# GyroscopeBreakout.net
KiCad netlist of a schematic drawn in Altium Designer
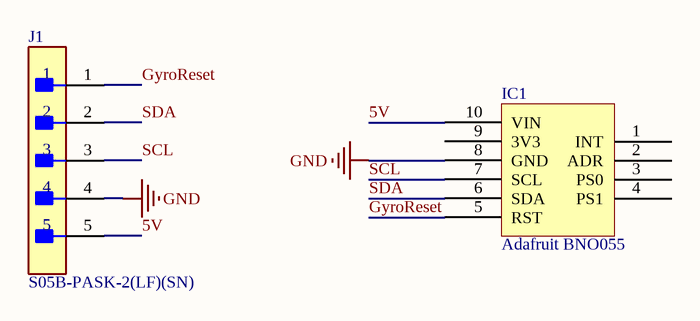
[diagram p0: GyroscopeBreakout.SchDoc]

(export (version "E")
  (design (tool "Eeschema 10.0.6"))
  (components
    (comp (ref "IC1")
      (value "Adafruit BNO055")
      (footprint "Adafruit BNO055-Footprint-1")
      (libsource (lib "Jouveer") (part "Adafruit BNO055-Symbol-1"))
    )
    (comp (ref "J1")
      (value "S05B-PASK-2(LF)(SN)")
      (footprint "FP-S05B-PASK-2_LF_SN-MFG")
      (description "CONN HEADER R/A 5POS 2MM")
      (libsource (lib "Altium Content Vault") (part "bf93c07fd2649a848d0ec8585582aab"))
    )
  )
  (nets
    (net (code "1") (name "/5V") (class "Default")
      (node (ref "IC1") (pin "10") (pinfunction "VIN_10") (pintype "passive"))
      (node (ref "J1") (pin "5") (pinfunction "5_5") (pintype "passive"))
    )
    (net (code "2") (name "/GyroReset") (class "Default")
      (node (ref "IC1") (pin "5") (pinfunction "RST_5") (pintype "passive"))
      (node (ref "J1") (pin "1") (pinfunction "1_1") (pintype "passive"))
    )
    (net (code "3") (name "/SCL") (class "Default")
      (node (ref "IC1") (pin "7") (pinfunction "SCL_7") (pintype "passive"))
      (node (ref "J1") (pin "3") (pinfunction "3_3") (pintype "passive"))
    )
    (net (code "4") (name "/SDA") (class "Default")
      (node (ref "IC1") (pin "6") (pinfunction "SDA_6") (pintype "passive"))
      (node (ref "J1") (pin "2") (pinfunction "2_2") (pintype "passive"))
    )
    (net (code "5") (name "GND") (class "Default")
      (node (ref "IC1") (pin "8") (pinfunction "GND_8") (pintype "passive"))
      (node (ref "J1") (pin "4") (pinfunction "4_4") (pintype "passive"))
    )
    (net (code "6") (name "unconnected-(IC1-3V3-Pad9)") (class "Default")
      (node (ref "IC1") (pin "9") (pinfunction "3V3_9") (pintype "passive"))
    )
    (net (code "7") (name "unconnected-(IC1-ADR-Pad2)") (class "Default")
      (node (ref "IC1") (pin "2") (pinfunction "ADR_2") (pintype "passive"))
    )
    (net (code "8") (name "unconnected-(IC1-INT-Pad1)") (class "Default")
      (node (ref "IC1") (pin "1") (pinfunction "INT_1") (pintype "passive"))
    )
    (net (code "9") (name "unconnected-(IC1-PS0-Pad3)") (class "Default")
      (node (ref "IC1") (pin "3") (pinfunction "PS0_3") (pintype "passive"))
    )
    (net (code "10") (name "unconnected-(IC1-PS1-Pad4)") (class "Default")
      (node (ref "IC1") (pin "4") (pinfunction "PS1_4") (pintype "passive"))
    )
  )
)
